# RPi_Color_Detector_PCB_v4.net
KiCad netlist of a schematic drawn in EAGLE
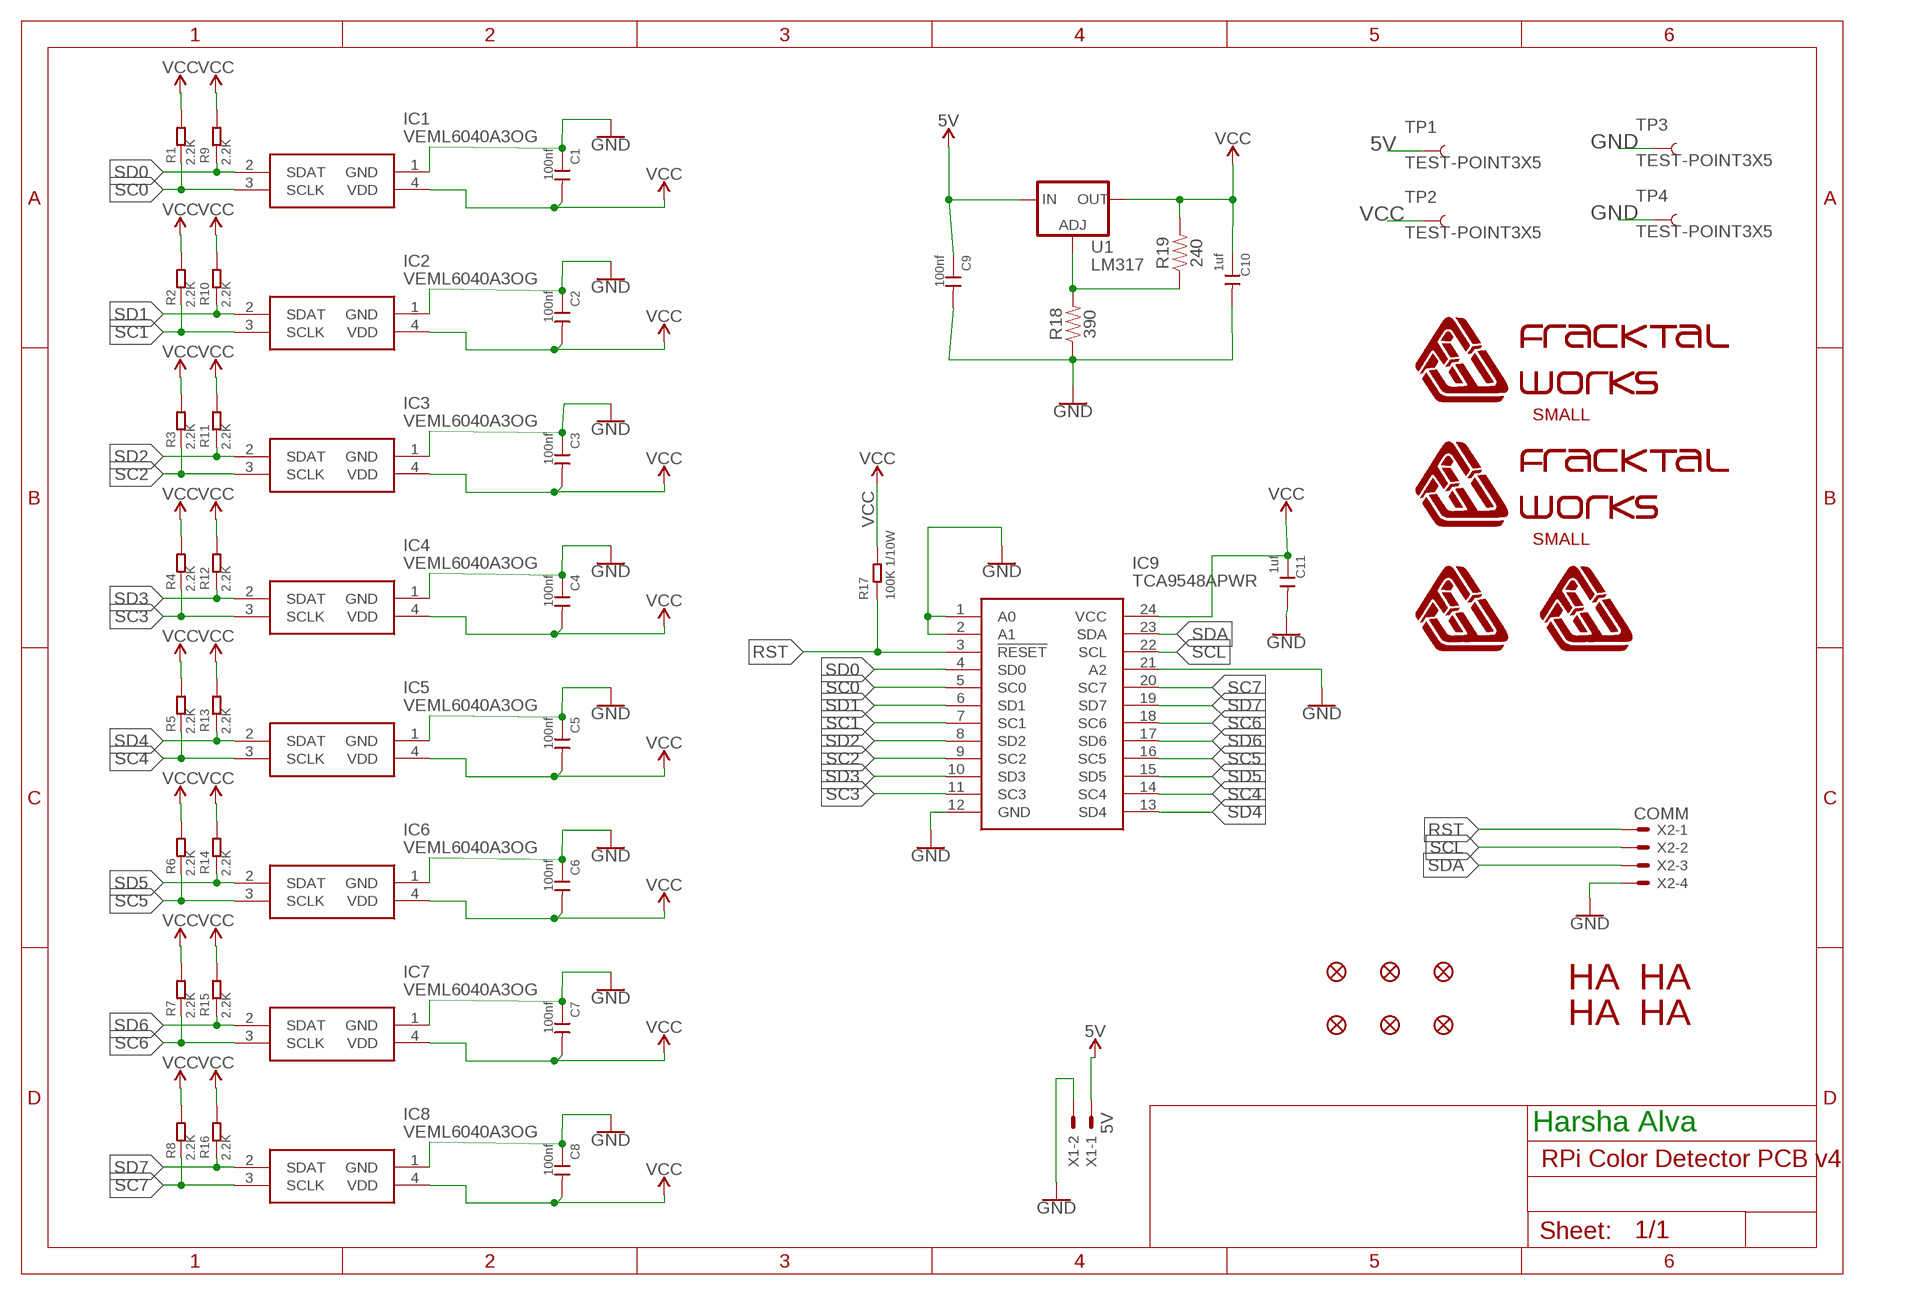
[diagram p0: schematic, sheet 1]

(export (version "E")
  (design (tool "Eeschema 10.0.6"))
  (components
    (comp (ref "C1")
      (value "100nf")
      (footprint "eagle-import:C0402")
      (fields (field (name "MPN") "CC0402KRX7R8BB104"))
      (libsource (lib "eagle-import") (part "CERAMIC-100NF-25V-10%-X7R(0402)"))
    )
    (comp (ref "C2")
      (value "100nf")
      (footprint "eagle-import:C0402")
      (fields (field (name "MPN") "CC0402KRX7R8BB104"))
      (libsource (lib "eagle-import") (part "CERAMIC-100NF-25V-10%-X7R(0402)"))
    )
    (comp (ref "C3")
      (value "100nf")
      (footprint "eagle-import:C0402")
      (fields (field (name "MPN") "CC0402KRX7R8BB104"))
      (libsource (lib "eagle-import") (part "CERAMIC-100NF-25V-10%-X7R(0402)"))
    )
    (comp (ref "C4")
      (value "100nf")
      (footprint "eagle-import:C0402")
      (fields (field (name "MPN") "CC0402KRX7R8BB104"))
      (libsource (lib "eagle-import") (part "CERAMIC-100NF-25V-10%-X7R(0402)"))
    )
    (comp (ref "C5")
      (value "100nf")
      (footprint "eagle-import:C0402")
      (fields (field (name "MPN") "CC0402KRX7R8BB104"))
      (libsource (lib "eagle-import") (part "CERAMIC-100NF-25V-10%-X7R(0402)"))
    )
    (comp (ref "C6")
      (value "100nf")
      (footprint "eagle-import:C0402")
      (fields (field (name "MPN") "CC0402KRX7R8BB104"))
      (libsource (lib "eagle-import") (part "CERAMIC-100NF-25V-10%-X7R(0402)"))
    )
    (comp (ref "C7")
      (value "100nf")
      (footprint "eagle-import:C0402")
      (fields (field (name "MPN") "CC0402KRX7R8BB104"))
      (libsource (lib "eagle-import") (part "CERAMIC-100NF-25V-10%-X7R(0402)"))
    )
    (comp (ref "C8")
      (value "100nf")
      (footprint "eagle-import:C0402")
      (fields (field (name "MPN") "CC0402KRX7R8BB104"))
      (libsource (lib "eagle-import") (part "CERAMIC-100NF-25V-10%-X7R(0402)"))
    )
    (comp (ref "C9")
      (value "100nf")
      (footprint "eagle-import:C0402")
      (fields (field (name "MPN") "CC0402KRX7R8BB104"))
      (libsource (lib "eagle-import") (part "CERAMIC-100NF-25V-10%-X7R(0402)"))
    )
    (comp (ref "C10")
      (value "1uf")
      (footprint "eagle-import:C0402")
      (fields (field (name "MPN") "CC0402KRX5R6BB105"))
      (libsource (lib "eagle-import") (part "CERAMIC-1UF-10V-10%-X5R(0402)"))
    )
    (comp (ref "C11")
      (value "1uf")
      (footprint "eagle-import:C0402")
      (fields (field (name "MPN") "CC0402KRX5R6BB105"))
      (libsource (lib "eagle-import") (part "CERAMIC-1UF-10V-10%-X5R(0402)"))
    )
    (comp (ref "FD1")
      (value "FIDUCIAL1X2")
      (footprint "eagle-import:FIDUCIAL-1X2")
      (libsource (lib "eagle-import") (part "FIDUCIAL1X2"))
    )
    (comp (ref "FD2")
      (value "FIDUCIAL1X2")
      (footprint "eagle-import:FIDUCIAL-1X2")
      (libsource (lib "eagle-import") (part "FIDUCIAL1X2"))
    )
    (comp (ref "FD3")
      (value "FIDUCIAL1X2")
      (footprint "eagle-import:FIDUCIAL-1X2")
      (libsource (lib "eagle-import") (part "FIDUCIAL1X2"))
    )
    (comp (ref "FD4")
      (value "FIDUCIAL1X2")
      (footprint "eagle-import:FIDUCIAL-1X2")
      (libsource (lib "eagle-import") (part "FIDUCIAL1X2"))
    )
    (comp (ref "FD5")
      (value "FIDUCIAL1X2")
      (footprint "eagle-import:FIDUCIAL-1X2")
      (libsource (lib "eagle-import") (part "FIDUCIAL1X2"))
    )
    (comp (ref "FD6")
      (value "FIDUCIAL1X2")
      (footprint "eagle-import:FIDUCIAL-1X2")
      (libsource (lib "eagle-import") (part "FIDUCIAL1X2"))
    )
    (comp (ref "FWLOGO_1")
      (value "FWLOGO")
      (footprint "eagle-import:FWLOGO")
      (libsource (lib "eagle-import") (part "FWLOGO"))
    )
    (comp (ref "FWLOGO_2")
      (value "FWLOGO")
      (footprint "eagle-import:FWLOGO")
      (libsource (lib "eagle-import") (part "FWLOGO"))
    )
    (comp (ref "FW_TXT_S_1")
      (value "FWLOGO_TEXT_SMALL")
      (footprint "eagle-import:FWLOGO_TEXT_SMALL")
      (libsource (lib "eagle-import") (part "FWLOGO_TEXT_SMALL"))
    )
    (comp (ref "FW_TXT_S_2")
      (value "FWLOGO_TEXT_SMALL")
      (footprint "eagle-import:FWLOGO_TEXT_SMALL")
      (libsource (lib "eagle-import") (part "FWLOGO_TEXT_SMALL"))
    )
    (comp (ref "IC1")
      (value "VEML6040A3OG")
      (footprint "eagle-import:VEML6040A3OG")
      (fields (field (name "MOUSER_PART_NUMBER") "78-VEML6040A3OG"))
      (libsource (lib "eagle-import") (part "VEML6040A3OG"))
    )
    (comp (ref "IC2")
      (value "VEML6040A3OG")
      (footprint "eagle-import:VEML6040A3OG")
      (fields (field (name "MOUSER_PART_NUMBER") "78-VEML6040A3OG"))
      (libsource (lib "eagle-import") (part "VEML6040A3OG"))
    )
    (comp (ref "IC3")
      (value "VEML6040A3OG")
      (footprint "eagle-import:VEML6040A3OG")
      (fields (field (name "MOUSER_PART_NUMBER") "78-VEML6040A3OG"))
      (libsource (lib "eagle-import") (part "VEML6040A3OG"))
    )
    (comp (ref "IC4")
      (value "VEML6040A3OG")
      (footprint "eagle-import:VEML6040A3OG")
      (fields (field (name "MOUSER_PART_NUMBER") "78-VEML6040A3OG"))
      (libsource (lib "eagle-import") (part "VEML6040A3OG"))
    )
    (comp (ref "IC5")
      (value "VEML6040A3OG")
      (footprint "eagle-import:VEML6040A3OG")
      (fields (field (name "MOUSER_PART_NUMBER") "78-VEML6040A3OG"))
      (libsource (lib "eagle-import") (part "VEML6040A3OG"))
    )
    (comp (ref "IC6")
      (value "VEML6040A3OG")
      (footprint "eagle-import:VEML6040A3OG")
      (fields (field (name "MOUSER_PART_NUMBER") "78-VEML6040A3OG"))
      (libsource (lib "eagle-import") (part "VEML6040A3OG"))
    )
    (comp (ref "IC7")
      (value "VEML6040A3OG")
      (footprint "eagle-import:VEML6040A3OG")
      (fields (field (name "MOUSER_PART_NUMBER") "78-VEML6040A3OG"))
      (libsource (lib "eagle-import") (part "VEML6040A3OG"))
    )
    (comp (ref "IC8")
      (value "VEML6040A3OG")
      (footprint "eagle-import:VEML6040A3OG")
      (fields (field (name "MOUSER_PART_NUMBER") "78-VEML6040A3OG"))
      (libsource (lib "eagle-import") (part "VEML6040A3OG"))
    )
    (comp (ref "IC9")
      (value "TCA9548APWR")
      (footprint "eagle-import:SOP65P640X120-24N")
      (fields (field (name "MOUSER_PART_NUMBER") "595-TCA9548APWR"))
      (libsource (lib "eagle-import") (part "TCA9548APWR"))
    )
    (comp (ref "M_HA_1")
      (value "HA_MARK")
      (footprint "eagle-import:HA_MARK")
      (libsource (lib "eagle-import") (part "HA_MARK"))
    )
    (comp (ref "M_HA_2")
      (value "HA_MARK")
      (footprint "eagle-import:HA_MARK")
      (libsource (lib "eagle-import") (part "HA_MARK"))
    )
    (comp (ref "M_HA_3")
      (value "HA_MARK")
      (footprint "eagle-import:HA_MARK")
      (libsource (lib "eagle-import") (part "HA_MARK"))
    )
    (comp (ref "M_HA_4")
      (value "HA_MARK")
      (footprint "eagle-import:HA_MARK")
      (libsource (lib "eagle-import") (part "HA_MARK"))
    )
    (comp (ref "R1")
      (value "2.2K")
      (footprint "eagle-import:R0603")
      (fields (field (name "MPN") "RC0603JR-072K2L"))
      (libsource (lib "eagle-import") (part "SMD-RES-2.2K-5%-1/10W(0603)"))
    )
    (comp (ref "R2")
      (value "2.2K")
      (footprint "eagle-import:R0603")
      (fields (field (name "MPN") "RC0603JR-072K2L"))
      (libsource (lib "eagle-import") (part "SMD-RES-2.2K-5%-1/10W(0603)"))
    )
    (comp (ref "R3")
      (value "2.2K")
      (footprint "eagle-import:R0603")
      (fields (field (name "MPN") "RC0603JR-072K2L"))
      (libsource (lib "eagle-import") (part "SMD-RES-2.2K-5%-1/10W(0603)"))
    )
    (comp (ref "R4")
      (value "2.2K")
      (footprint "eagle-import:R0603")
      (fields (field (name "MPN") "RC0603JR-072K2L"))
      (libsource (lib "eagle-import") (part "SMD-RES-2.2K-5%-1/10W(0603)"))
    )
    (comp (ref "R5")
      (value "2.2K")
      (footprint "eagle-import:R0603")
      (fields (field (name "MPN") "RC0603JR-072K2L"))
      (libsource (lib "eagle-import") (part "SMD-RES-2.2K-5%-1/10W(0603)"))
    )
    (comp (ref "R6")
      (value "2.2K")
      (footprint "eagle-import:R0603")
      (fields (field (name "MPN") "RC0603JR-072K2L"))
      (libsource (lib "eagle-import") (part "SMD-RES-2.2K-5%-1/10W(0603)"))
    )
    (comp (ref "R7")
      (value "2.2K")
      (footprint "eagle-import:R0603")
      (fields (field (name "MPN") "RC0603JR-072K2L"))
      (libsource (lib "eagle-import") (part "SMD-RES-2.2K-5%-1/10W(0603)"))
    )
    (comp (ref "R8")
      (value "2.2K")
      (footprint "eagle-import:R0603")
      (fields (field (name "MPN") "RC0603JR-072K2L"))
      (libsource (lib "eagle-import") (part "SMD-RES-2.2K-5%-1/10W(0603)"))
    )
    (comp (ref "R9")
      (value "2.2K")
      (footprint "eagle-import:R0603")
      (fields (field (name "MPN") "RC0603JR-072K2L"))
      (libsource (lib "eagle-import") (part "SMD-RES-2.2K-5%-1/10W(0603)"))
    )
    (comp (ref "R10")
      (value "2.2K")
      (footprint "eagle-import:R0603")
      (fields (field (name "MPN") "RC0603JR-072K2L"))
      (libsource (lib "eagle-import") (part "SMD-RES-2.2K-5%-1/10W(0603)"))
    )
    (comp (ref "R11")
      (value "2.2K")
      (footprint "eagle-import:R0603")
      (fields (field (name "MPN") "RC0603JR-072K2L"))
      (libsource (lib "eagle-import") (part "SMD-RES-2.2K-5%-1/10W(0603)"))
    )
    (comp (ref "R12")
      (value "2.2K")
      (footprint "eagle-import:R0603")
      (fields (field (name "MPN") "RC0603JR-072K2L"))
      (libsource (lib "eagle-import") (part "SMD-RES-2.2K-5%-1/10W(0603)"))
    )
    (comp (ref "R13")
      (value "2.2K")
      (footprint "eagle-import:R0603")
      (fields (field (name "MPN") "RC0603JR-072K2L"))
      (libsource (lib "eagle-import") (part "SMD-RES-2.2K-5%-1/10W(0603)"))
    )
    (comp (ref "R14")
      (value "2.2K")
      (footprint "eagle-import:R0603")
      (fields (field (name "MPN") "RC0603JR-072K2L"))
      (libsource (lib "eagle-import") (part "SMD-RES-2.2K-5%-1/10W(0603)"))
    )
    (comp (ref "R15")
      (value "2.2K")
      (footprint "eagle-import:R0603")
      (fields (field (name "MPN") "RC0603JR-072K2L"))
      (libsource (lib "eagle-import") (part "SMD-RES-2.2K-5%-1/10W(0603)"))
    )
    (comp (ref "R16")
      (value "2.2K")
      (footprint "eagle-import:R0603")
      (fields (field (name "MPN") "RC0603JR-072K2L"))
      (libsource (lib "eagle-import") (part "SMD-RES-2.2K-5%-1/10W(0603)"))
    )
    (comp (ref "R17")
      (value "100K 1/10W")
      (footprint "eagle-import:R0603")
      (fields (field (name "MPN") "RC0603JR-07100KL"))
      (libsource (lib "eagle-import") (part "SMD-RES-100K-5%-1/10W(0603)"))
    )
    (comp (ref "R18")
      (value "390")
      (footprint "eagle-import:0603")
      (libsource (lib "eagle-import") (part "RESISTOR0603"))
    )
    (comp (ref "R19")
      (value "240")
      (footprint "eagle-import:0603")
      (libsource (lib "eagle-import") (part "RESISTOR0603"))
    )
    (comp (ref "TP1")
      (value "TEST-POINT3X5")
      (footprint "eagle-import:PAD.03X.05")
      (libsource (lib "eagle-import") (part "TEST-POINT3X5"))
    )
    (comp (ref "TP2")
      (value "TEST-POINT3X5")
      (footprint "eagle-import:PAD.03X.05")
      (libsource (lib "eagle-import") (part "TEST-POINT3X5"))
    )
    (comp (ref "TP3")
      (value "TEST-POINT3X5")
      (footprint "eagle-import:PAD.03X.05")
      (libsource (lib "eagle-import") (part "TEST-POINT3X5"))
    )
    (comp (ref "TP4")
      (value "TEST-POINT3X5")
      (footprint "eagle-import:PAD.03X.05")
      (libsource (lib "eagle-import") (part "TEST-POINT3X5"))
    )
    (comp (ref "U1")
      (value "LM317")
      (footprint "eagle-import:SOT223")
      (libsource (lib "eagle-import") (part "V_REG_317SMD"))
    )
    (comp (ref "X1")
      (value "5V")
      (footprint "eagle-import:JST-XH-02-PACKAGE-LONG-PAD")
      (libsource (lib "eagle-import") (part "JST-XH-02-PIN-LONG-PAD"))
    )
    (comp (ref "X2")
      (value "COMM")
      (footprint "eagle-import:JST-XH-04-PACKAGE-ROUND-PAD")
      (libsource (lib "eagle-import") (part "JST-XH-04-PIN-ROUND-PAD"))
    )
  )
  (nets
    (net (code "1") (name "5V") (class "Default")
      (node (ref "C9") (pin "1") (pinfunction "1_1") (pintype "passive"))
      (node (ref "TP1") (pin "P$1") (pinfunction "1_P$1") (pintype "bidirectional"))
      (node (ref "U1") (pin "3") (pinfunction "IN_3") (pintype "input"))
      (node (ref "X1") (pin "1") (pinfunction "S_1") (pintype "passive"))
    )
    (net (code "2") (name "GND") (class "Default")
      (node (ref "C1") (pin "1") (pinfunction "1_1") (pintype "passive"))
      (node (ref "C10") (pin "2") (pinfunction "2_2") (pintype "passive"))
      (node (ref "C11") (pin "2") (pinfunction "2_2") (pintype "passive"))
      (node (ref "C2") (pin "1") (pinfunction "1_1") (pintype "passive"))
      (node (ref "C3") (pin "1") (pinfunction "1_1") (pintype "passive"))
      (node (ref "C4") (pin "1") (pinfunction "1_1") (pintype "passive"))
      (node (ref "C5") (pin "1") (pinfunction "1_1") (pintype "passive"))
      (node (ref "C6") (pin "1") (pinfunction "1_1") (pintype "passive"))
      (node (ref "C7") (pin "1") (pinfunction "1_1") (pintype "passive"))
      (node (ref "C8") (pin "1") (pinfunction "1_1") (pintype "passive"))
      (node (ref "C9") (pin "2") (pinfunction "2_2") (pintype "passive"))
      (node (ref "IC1") (pin "1") (pinfunction "GND_1") (pintype "bidirectional"))
      (node (ref "IC2") (pin "1") (pinfunction "GND_1") (pintype "bidirectional"))
      (node (ref "IC3") (pin "1") (pinfunction "GND_1") (pintype "bidirectional"))
      (node (ref "IC4") (pin "1") (pinfunction "GND_1") (pintype "bidirectional"))
      (node (ref "IC5") (pin "1") (pinfunction "GND_1") (pintype "bidirectional"))
      (node (ref "IC6") (pin "1") (pinfunction "GND_1") (pintype "bidirectional"))
      (node (ref "IC7") (pin "1") (pinfunction "GND_1") (pintype "bidirectional"))
      (node (ref "IC8") (pin "1") (pinfunction "GND_1") (pintype "bidirectional"))
      (node (ref "IC9") (pin "1") (pinfunction "A0_1") (pintype "bidirectional"))
      (node (ref "IC9") (pin "12") (pinfunction "GND_12") (pintype "bidirectional"))
      (node (ref "IC9") (pin "2") (pinfunction "A1_2") (pintype "bidirectional"))
      (node (ref "IC9") (pin "21") (pinfunction "A2_21") (pintype "bidirectional"))
      (node (ref "R18") (pin "1") (pinfunction "1_1") (pintype "passive"))
      (node (ref "TP3") (pin "P$1") (pinfunction "1_P$1") (pintype "bidirectional"))
      (node (ref "TP4") (pin "P$1") (pinfunction "1_P$1") (pintype "bidirectional"))
      (node (ref "X1") (pin "2") (pinfunction "S_2") (pintype "passive"))
      (node (ref "X2") (pin "4") (pinfunction "S_4") (pintype "passive"))
    )
    (net (code "3") (name "Net-(U1-ADJ)") (class "Default")
      (node (ref "R18") (pin "2") (pinfunction "2_2") (pintype "passive"))
      (node (ref "R19") (pin "1") (pinfunction "1_1") (pintype "passive"))
      (node (ref "U1") (pin "1") (pinfunction "ADJ_1") (pintype "input"))
    )
    (net (code "4") (name "RST") (class "Default")
      (node (ref "IC9") (pin "3") (pinfunction "~{RESET}_3") (pintype "bidirectional"))
      (node (ref "R17") (pin "1") (pinfunction "1_1") (pintype "passive"))
      (node (ref "X2") (pin "1") (pinfunction "S_1") (pintype "passive"))
    )
    (net (code "5") (name "SC0") (class "Default")
      (node (ref "IC1") (pin "3") (pinfunction "SCLK_3") (pintype "bidirectional"))
      (node (ref "IC9") (pin "5") (pinfunction "SC0_5") (pintype "bidirectional"))
      (node (ref "R1") (pin "1") (pinfunction "1_1") (pintype "passive"))
    )
    (net (code "6") (name "SC1") (class "Default")
      (node (ref "IC2") (pin "3") (pinfunction "SCLK_3") (pintype "bidirectional"))
      (node (ref "IC9") (pin "7") (pinfunction "SC1_7") (pintype "bidirectional"))
      (node (ref "R2") (pin "1") (pinfunction "1_1") (pintype "passive"))
    )
    (net (code "7") (name "SC2") (class "Default")
      (node (ref "IC3") (pin "3") (pinfunction "SCLK_3") (pintype "bidirectional"))
      (node (ref "IC9") (pin "9") (pinfunction "SC2_9") (pintype "bidirectional"))
      (node (ref "R3") (pin "1") (pinfunction "1_1") (pintype "passive"))
    )
    (net (code "8") (name "SC3") (class "Default")
      (node (ref "IC4") (pin "3") (pinfunction "SCLK_3") (pintype "bidirectional"))
      (node (ref "IC9") (pin "11") (pinfunction "SC3_11") (pintype "bidirectional"))
      (node (ref "R4") (pin "1") (pinfunction "1_1") (pintype "passive"))
    )
    (net (code "9") (name "SC4") (class "Default")
      (node (ref "IC5") (pin "3") (pinfunction "SCLK_3") (pintype "bidirectional"))
      (node (ref "IC9") (pin "14") (pinfunction "SC4_14") (pintype "bidirectional"))
      (node (ref "R5") (pin "1") (pinfunction "1_1") (pintype "passive"))
    )
    (net (code "10") (name "SC5") (class "Default")
      (node (ref "IC6") (pin "3") (pinfunction "SCLK_3") (pintype "bidirectional"))
      (node (ref "IC9") (pin "16") (pinfunction "SC5_16") (pintype "bidirectional"))
      (node (ref "R6") (pin "1") (pinfunction "1_1") (pintype "passive"))
    )
    (net (code "11") (name "SC6") (class "Default")
      (node (ref "IC7") (pin "3") (pinfunction "SCLK_3") (pintype "bidirectional"))
      (node (ref "IC9") (pin "18") (pinfunction "SC6_18") (pintype "bidirectional"))
      (node (ref "R7") (pin "1") (pinfunction "1_1") (pintype "passive"))
    )
    (net (code "12") (name "SC7") (class "Default")
      (node (ref "IC8") (pin "3") (pinfunction "SCLK_3") (pintype "bidirectional"))
      (node (ref "IC9") (pin "20") (pinfunction "SC7_20") (pintype "bidirectional"))
      (node (ref "R8") (pin "1") (pinfunction "1_1") (pintype "passive"))
    )
    (net (code "13") (name "SCL") (class "Default")
      (node (ref "IC9") (pin "22") (pinfunction "SCL_22") (pintype "bidirectional"))
      (node (ref "X2") (pin "2") (pinfunction "S_2") (pintype "passive"))
    )
    (net (code "14") (name "SD0") (class "Default")
      (node (ref "IC1") (pin "2") (pinfunction "SDAT_2") (pintype "bidirectional"))
      (node (ref "IC9") (pin "4") (pinfunction "SD0_4") (pintype "bidirectional"))
      (node (ref "R9") (pin "1") (pinfunction "1_1") (pintype "passive"))
    )
    (net (code "15") (name "SD1") (class "Default")
      (node (ref "IC2") (pin "2") (pinfunction "SDAT_2") (pintype "bidirectional"))
      (node (ref "IC9") (pin "6") (pinfunction "SD1_6") (pintype "bidirectional"))
      (node (ref "R10") (pin "1") (pinfunction "1_1") (pintype "passive"))
    )
    (net (code "16") (name "SD2") (class "Default")
      (node (ref "IC3") (pin "2") (pinfunction "SDAT_2") (pintype "bidirectional"))
      (node (ref "IC9") (pin "8") (pinfunction "SD2_8") (pintype "bidirectional"))
      (node (ref "R11") (pin "1") (pinfunction "1_1") (pintype "passive"))
    )
    (net (code "17") (name "SD3") (class "Default")
      (node (ref "IC4") (pin "2") (pinfunction "SDAT_2") (pintype "bidirectional"))
      (node (ref "IC9") (pin "10") (pinfunction "SD3_10") (pintype "bidirectional"))
      (node (ref "R12") (pin "1") (pinfunction "1_1") (pintype "passive"))
    )
    (net (code "18") (name "SD4") (class "Default")
      (node (ref "IC5") (pin "2") (pinfunction "SDAT_2") (pintype "bidirectional"))
      (node (ref "IC9") (pin "13") (pinfunction "SD4_13") (pintype "bidirectional"))
      (node (ref "R13") (pin "1") (pinfunction "1_1") (pintype "passive"))
    )
    (net (code "19") (name "SD5") (class "Default")
      (node (ref "IC6") (pin "2") (pinfunction "SDAT_2") (pintype "bidirectional"))
      (node (ref "IC9") (pin "15") (pinfunction "SD5_15") (pintype "bidirectional"))
      (node (ref "R14") (pin "1") (pinfunction "1_1") (pintype "passive"))
    )
    (net (code "20") (name "SD6") (class "Default")
      (node (ref "IC7") (pin "2") (pinfunction "SDAT_2") (pintype "bidirectional"))
      (node (ref "IC9") (pin "17") (pinfunction "SD6_17") (pintype "bidirectional"))
      (node (ref "R15") (pin "1") (pinfunction "1_1") (pintype "passive"))
    )
    (net (code "21") (name "SD7") (class "Default")
      (node (ref "IC8") (pin "2") (pinfunction "SDAT_2") (pintype "bidirectional"))
      (node (ref "IC9") (pin "19") (pinfunction "SD7_19") (pintype "bidirectional"))
      (node (ref "R16") (pin "1") (pinfunction "1_1") (pintype "passive"))
    )
    (net (code "22") (name "SDA") (class "Default")
      (node (ref "IC9") (pin "23") (pinfunction "SDA_23") (pintype "bidirectional"))
      (node (ref "X2") (pin "3") (pinfunction "S_3") (pintype "passive"))
    )
    (net (code "23") (name "VCC") (class "Default")
      (node (ref "C1") (pin "2") (pinfunction "2_2") (pintype "passive"))
      (node (ref "C10") (pin "1") (pinfunction "1_1") (pintype "passive"))
      (node (ref "C11") (pin "1") (pinfunction "1_1") (pintype "passive"))
      (node (ref "C2") (pin "2") (pinfunction "2_2") (pintype "passive"))
      (node (ref "C3") (pin "2") (pinfunction "2_2") (pintype "passive"))
      (node (ref "C4") (pin "2") (pinfunction "2_2") (pintype "passive"))
      (node (ref "C5") (pin "2") (pinfunction "2_2") (pintype "passive"))
      (node (ref "C6") (pin "2") (pinfunction "2_2") (pintype "passive"))
      (node (ref "C7") (pin "2") (pinfunction "2_2") (pintype "passive"))
      (node (ref "C8") (pin "2") (pinfunction "2_2") (pintype "passive"))
      (node (ref "IC1") (pin "4") (pinfunction "VDD_4") (pintype "bidirectional"))
      (node (ref "IC2") (pin "4") (pinfunction "VDD_4") (pintype "bidirectional"))
      (node (ref "IC3") (pin "4") (pinfunction "VDD_4") (pintype "bidirectional"))
      (node (ref "IC4") (pin "4") (pinfunction "VDD_4") (pintype "bidirectional"))
      (node (ref "IC5") (pin "4") (pinfunction "VDD_4") (pintype "bidirectional"))
      (node (ref "IC6") (pin "4") (pinfunction "VDD_4") (pintype "bidirectional"))
      (node (ref "IC7") (pin "4") (pinfunction "VDD_4") (pintype "bidirectional"))
      (node (ref "IC8") (pin "4") (pinfunction "VDD_4") (pintype "bidirectional"))
      (node (ref "IC9") (pin "24") (pinfunction "VCC_24") (pintype "bidirectional"))
      (node (ref "R1") (pin "2") (pinfunction "2_2") (pintype "passive"))
      (node (ref "R10") (pin "2") (pinfunction "2_2") (pintype "passive"))
      (node (ref "R11") (pin "2") (pinfunction "2_2") (pintype "passive"))
      (node (ref "R12") (pin "2") (pinfunction "2_2") (pintype "passive"))
      (node (ref "R13") (pin "2") (pinfunction "2_2") (pintype "passive"))
      (node (ref "R14") (pin "2") (pinfunction "2_2") (pintype "passive"))
      (node (ref "R15") (pin "2") (pinfunction "2_2") (pintype "passive"))
      (node (ref "R16") (pin "2") (pinfunction "2_2") (pintype "passive"))
      (node (ref "R17") (pin "2") (pinfunction "2_2") (pintype "passive"))
      (node (ref "R19") (pin "2") (pinfunction "2_2") (pintype "passive"))
      (node (ref "R2") (pin "2") (pinfunction "2_2") (pintype "passive"))
      (node (ref "R3") (pin "2") (pinfunction "2_2") (pintype "passive"))
      (node (ref "R4") (pin "2") (pinfunction "2_2") (pintype "passive"))
      (node (ref "R5") (pin "2") (pinfunction "2_2") (pintype "passive"))
      (node (ref "R6") (pin "2") (pinfunction "2_2") (pintype "passive"))
      (node (ref "R7") (pin "2") (pinfunction "2_2") (pintype "passive"))
      (node (ref "R8") (pin "2") (pinfunction "2_2") (pintype "passive"))
      (node (ref "R9") (pin "2") (pinfunction "2_2") (pintype "passive"))
      (node (ref "TP2") (pin "P$1") (pinfunction "1_P$1") (pintype "bidirectional"))
      (node (ref "U1") (pin "2") (pinfunction "OUT_2") (pintype "output"))
    )
  )
)
